# MCU.net
KiCad netlist of a schematic drawn in Altium Designer
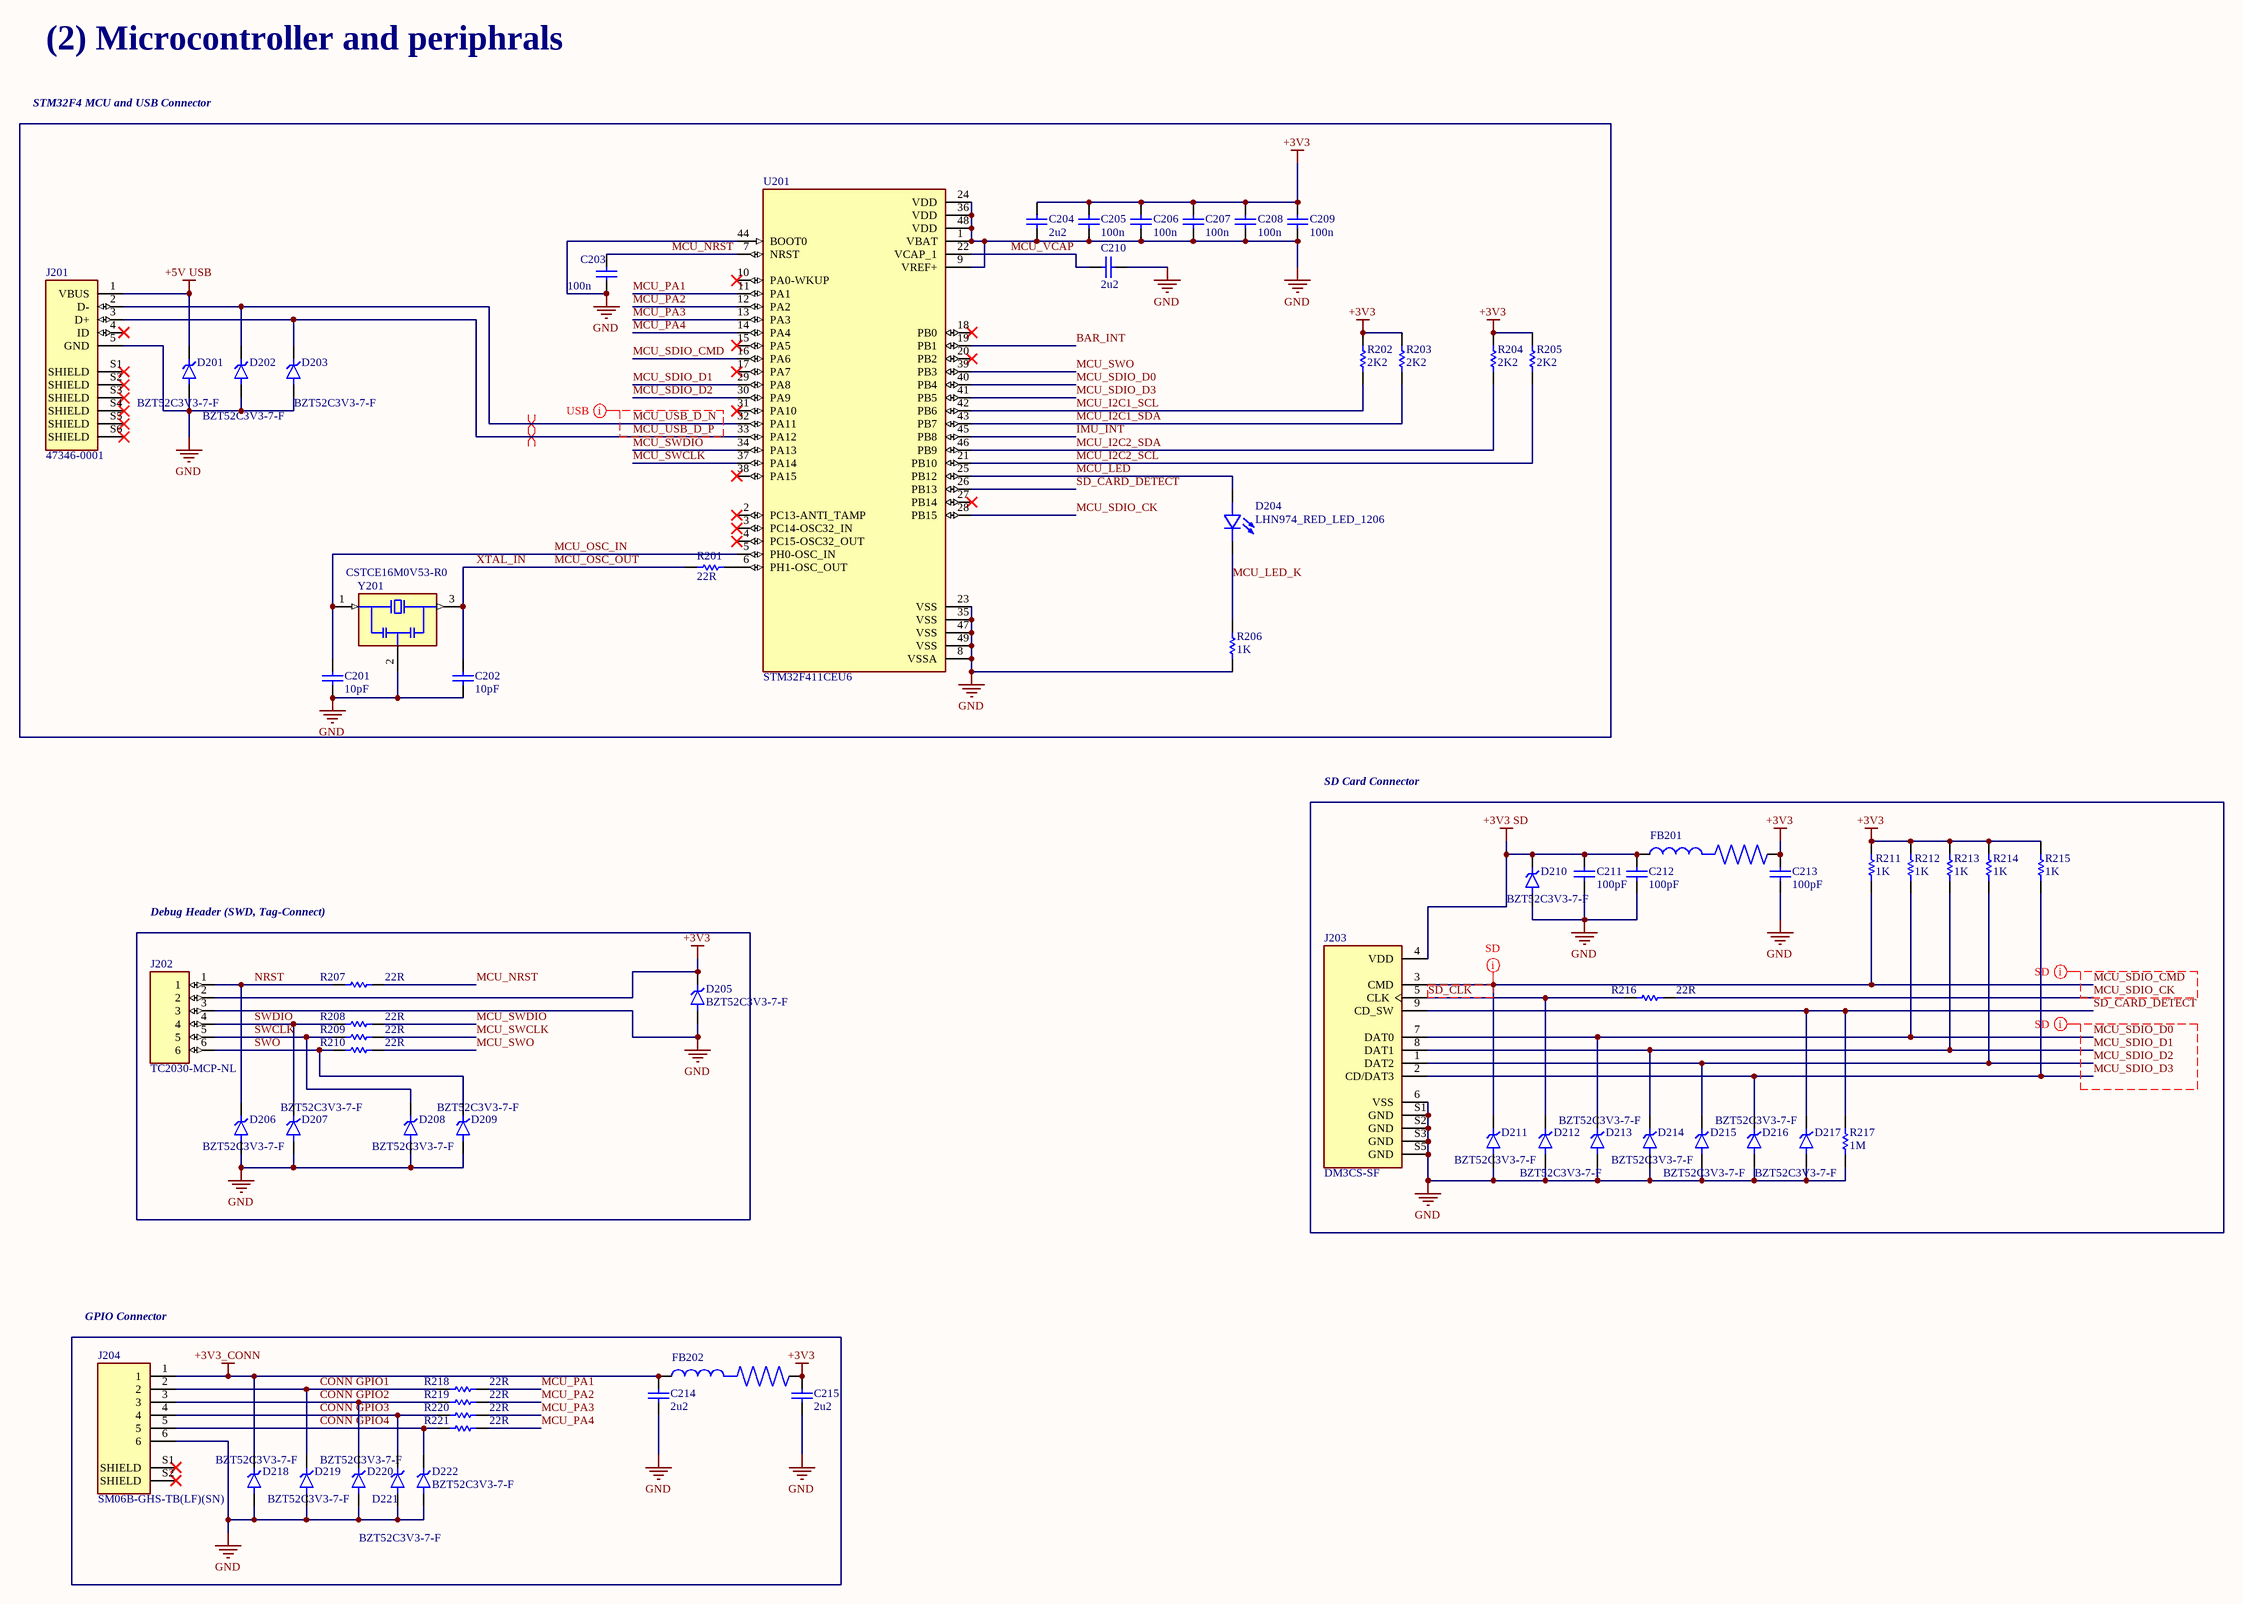
[diagram p0: MCU.SchDoc]

(export (version "E")
  (design (tool "Eeschema 10.0.6"))
  (components
    (comp (ref "C201")
      (value "10pF")
      (footprint "CAP-SM-0805")
      (description "Capacitor")
      (fields (field (name "Comment") "Cap Non-Pol SMD"))
      (libsource (lib "PIF_Library") (part "Cap Non-Pol SMD"))
    )
    (comp (ref "C202")
      (value "10pF")
      (footprint "CAP-SM-0805")
      (description "Capacitor")
      (fields (field (name "Comment") "Cap Non-Pol SMD"))
      (libsource (lib "PIF_Library") (part "Cap Non-Pol SMD"))
    )
    (comp (ref "C203")
      (value "100n")
      (footprint "CAP-SM-0805")
      (description "Capacitor")
      (fields (field (name "Comment") "Cap Non-Pol SMD"))
      (libsource (lib "PIF_Library") (part "Cap Non-Pol SMD"))
    )
    (comp (ref "C204")
      (value "2u2")
      (footprint "CAP-SM-0805")
      (description "Capacitor")
      (fields (field (name "Comment") "Cap Non-Pol SMD"))
      (libsource (lib "PIF_Library") (part "Cap Non-Pol SMD"))
    )
    (comp (ref "C205")
      (value "100n")
      (footprint "CAP-SM-0805")
      (description "Capacitor")
      (fields (field (name "Comment") "Cap Non-Pol SMD"))
      (libsource (lib "PIF_Library") (part "Cap Non-Pol SMD"))
    )
    (comp (ref "C206")
      (value "100n")
      (footprint "CAP-SM-0805")
      (description "Capacitor")
      (fields (field (name "Comment") "Cap Non-Pol SMD"))
      (libsource (lib "PIF_Library") (part "Cap Non-Pol SMD"))
    )
    (comp (ref "C207")
      (value "100n")
      (footprint "CAP-SM-0805")
      (description "Capacitor")
      (fields (field (name "Comment") "Cap Non-Pol SMD"))
      (libsource (lib "PIF_Library") (part "Cap Non-Pol SMD"))
    )
    (comp (ref "C208")
      (value "100n")
      (footprint "CAP-SM-0805")
      (description "Capacitor")
      (fields (field (name "Comment") "Cap Non-Pol SMD"))
      (libsource (lib "PIF_Library") (part "Cap Non-Pol SMD"))
    )
    (comp (ref "C209")
      (value "100n")
      (footprint "CAP-SM-0805")
      (description "Capacitor")
      (fields (field (name "Comment") "Cap Non-Pol SMD"))
      (libsource (lib "PIF_Library") (part "Cap Non-Pol SMD"))
    )
    (comp (ref "C210")
      (value "2u2")
      (footprint "CAP-SM-0805")
      (description "Capacitor")
      (fields (field (name "Comment") "Cap Non-Pol SMD"))
      (libsource (lib "PIF_Library") (part "Cap Non-Pol SMD"))
    )
    (comp (ref "C211")
      (value "100pF")
      (footprint "CAP-SM-0805")
      (description "Capacitor")
      (fields (field (name "Comment") "Cap Non-Pol SMD"))
      (libsource (lib "PIF_Library") (part "Cap Non-Pol SMD"))
    )
    (comp (ref "C212")
      (value "100pF")
      (footprint "CAP-SM-0805")
      (description "Capacitor")
      (fields (field (name "Comment") "Cap Non-Pol SMD"))
      (libsource (lib "PIF_Library") (part "Cap Non-Pol SMD"))
    )
    (comp (ref "C213")
      (value "100pF")
      (footprint "CAP-SM-0805")
      (description "Capacitor")
      (fields (field (name "Comment") "Cap Non-Pol SMD"))
      (libsource (lib "PIF_Library") (part "Cap Non-Pol SMD"))
    )
    (comp (ref "C214")
      (value "2u2")
      (footprint "CAP-SM-0805")
      (description "Capacitor")
      (fields (field (name "Comment") "Cap Non-Pol SMD"))
      (libsource (lib "PIF_Library") (part "Cap Non-Pol SMD"))
    )
    (comp (ref "C215")
      (value "2u2")
      (footprint "CAP-SM-0805")
      (description "Capacitor")
      (fields (field (name "Comment") "Cap Non-Pol SMD"))
      (libsource (lib "PIF_Library") (part "Cap Non-Pol SMD"))
    )
    (comp (ref "D201")
      (value "BZT52C3V3-7-F")
      (footprint "SOD3715X135N")
      (description "Diode Zener 3.3V 6% 500mW 2Pin SOD123 ¦ Diodes Inc BZT52C3V3-7-F")
      (fields (field (name "MF") "Diodes Inc."))
      (libsource (lib "BZT52C3V3-7-F") (part "BZT52C3V3-7-F"))
    )
    (comp (ref "D202")
      (value "BZT52C3V3-7-F")
      (footprint "SOD3715X135N")
      (description "Diode Zener 3.3V 6% 500mW 2Pin SOD123 ¦ Diodes Inc BZT52C3V3-7-F")
      (fields (field (name "MF") "Diodes Inc."))
      (libsource (lib "BZT52C3V3-7-F") (part "BZT52C3V3-7-F"))
    )
    (comp (ref "D203")
      (value "BZT52C3V3-7-F")
      (footprint "SOD3715X135N")
      (description "Diode Zener 3.3V 6% 500mW 2Pin SOD123 ¦ Diodes Inc BZT52C3V3-7-F")
      (fields (field (name "MF") "Diodes Inc."))
      (libsource (lib "BZT52C3V3-7-F") (part "BZT52C3V3-7-F"))
    )
    (comp (ref "D204")
      (value "LHN974_RED_LED_1206")
      (footprint "LEDC3216X120N")
      (description "2.6 V Red LED SMD")
      (fields (field (name "MF") "Osram") (field (name "MP") "LHN974 RED LED 1206"))
      (libsource (lib "LHN974_RED_LED_1206") (part "LHN974_RED_LED_1206"))
    )
    (comp (ref "D205")
      (value "BZT52C3V3-7-F")
      (footprint "SOD3715X135N")
      (description "Diode Zener 3.3V 6% 500mW 2Pin SOD123 ¦ Diodes Inc BZT52C3V3-7-F")
      (fields (field (name "MF") "Diodes Inc."))
      (libsource (lib "BZT52C3V3-7-F") (part "BZT52C3V3-7-F"))
    )
    (comp (ref "D206")
      (value "BZT52C3V3-7-F")
      (footprint "SOD3715X135N")
      (description "Diode Zener 3.3V 6% 500mW 2Pin SOD123 ¦ Diodes Inc BZT52C3V3-7-F")
      (fields (field (name "MF") "Diodes Inc."))
      (libsource (lib "BZT52C3V3-7-F") (part "BZT52C3V3-7-F"))
    )
    (comp (ref "D207")
      (value "BZT52C3V3-7-F")
      (footprint "SOD3715X135N")
      (description "Diode Zener 3.3V 6% 500mW 2Pin SOD123 ¦ Diodes Inc BZT52C3V3-7-F")
      (fields (field (name "MF") "Diodes Inc."))
      (libsource (lib "BZT52C3V3-7-F") (part "BZT52C3V3-7-F"))
    )
    (comp (ref "D208")
      (value "BZT52C3V3-7-F")
      (footprint "SOD3715X135N")
      (description "Diode Zener 3.3V 6% 500mW 2Pin SOD123 ¦ Diodes Inc BZT52C3V3-7-F")
      (fields (field (name "MF") "Diodes Inc."))
      (libsource (lib "BZT52C3V3-7-F") (part "BZT52C3V3-7-F"))
    )
    (comp (ref "D209")
      (value "BZT52C3V3-7-F")
      (footprint "SOD3715X135N")
      (description "Diode Zener 3.3V 6% 500mW 2Pin SOD123 ¦ Diodes Inc BZT52C3V3-7-F")
      (fields (field (name "MF") "Diodes Inc."))
      (libsource (lib "BZT52C3V3-7-F") (part "BZT52C3V3-7-F"))
    )
    (comp (ref "D210")
      (value "BZT52C3V3-7-F")
      (footprint "SOD3715X135N")
      (description "Diode Zener 3.3V 6% 500mW 2Pin SOD123 ¦ Diodes Inc BZT52C3V3-7-F")
      (fields (field (name "MF") "Diodes Inc."))
      (libsource (lib "BZT52C3V3-7-F") (part "BZT52C3V3-7-F"))
    )
    (comp (ref "D211")
      (value "BZT52C3V3-7-F")
      (footprint "SOD3715X135N")
      (description "Diode Zener 3.3V 6% 500mW 2Pin SOD123 ¦ Diodes Inc BZT52C3V3-7-F")
      (fields (field (name "MF") "Diodes Inc."))
      (libsource (lib "BZT52C3V3-7-F") (part "BZT52C3V3-7-F"))
    )
    (comp (ref "D212")
      (value "BZT52C3V3-7-F")
      (footprint "SOD3715X135N")
      (description "Diode Zener 3.3V 6% 500mW 2Pin SOD123 ¦ Diodes Inc BZT52C3V3-7-F")
      (fields (field (name "MF") "Diodes Inc."))
      (libsource (lib "BZT52C3V3-7-F") (part "BZT52C3V3-7-F"))
    )
    (comp (ref "D213")
      (value "BZT52C3V3-7-F")
      (footprint "SOD3715X135N")
      (description "Diode Zener 3.3V 6% 500mW 2Pin SOD123 ¦ Diodes Inc BZT52C3V3-7-F")
      (fields (field (name "MF") "Diodes Inc."))
      (libsource (lib "BZT52C3V3-7-F") (part "BZT52C3V3-7-F"))
    )
    (comp (ref "D214")
      (value "BZT52C3V3-7-F")
      (footprint "SOD3715X135N")
      (description "Diode Zener 3.3V 6% 500mW 2Pin SOD123 ¦ Diodes Inc BZT52C3V3-7-F")
      (fields (field (name "MF") "Diodes Inc."))
      (libsource (lib "BZT52C3V3-7-F") (part "BZT52C3V3-7-F"))
    )
    (comp (ref "D215")
      (value "BZT52C3V3-7-F")
      (footprint "SOD3715X135N")
      (description "Diode Zener 3.3V 6% 500mW 2Pin SOD123 ¦ Diodes Inc BZT52C3V3-7-F")
      (fields (field (name "MF") "Diodes Inc."))
      (libsource (lib "BZT52C3V3-7-F") (part "BZT52C3V3-7-F"))
    )
    (comp (ref "D216")
      (value "BZT52C3V3-7-F")
      (footprint "SOD3715X135N")
      (description "Diode Zener 3.3V 6% 500mW 2Pin SOD123 ¦ Diodes Inc BZT52C3V3-7-F")
      (fields (field (name "MF") "Diodes Inc."))
      (libsource (lib "BZT52C3V3-7-F") (part "BZT52C3V3-7-F"))
    )
    (comp (ref "D217")
      (value "BZT52C3V3-7-F")
      (footprint "SOD3715X135N")
      (description "Diode Zener 3.3V 6% 500mW 2Pin SOD123 ¦ Diodes Inc BZT52C3V3-7-F")
      (fields (field (name "MF") "Diodes Inc."))
      (libsource (lib "BZT52C3V3-7-F") (part "BZT52C3V3-7-F"))
    )
    (comp (ref "D218")
      (value "BZT52C3V3-7-F")
      (footprint "SOD3715X135N")
      (description "Diode Zener 3.3V 6% 500mW 2Pin SOD123 ¦ Diodes Inc BZT52C3V3-7-F")
      (fields (field (name "MF") "Diodes Inc."))
      (libsource (lib "BZT52C3V3-7-F") (part "BZT52C3V3-7-F"))
    )
    (comp (ref "D219")
      (value "BZT52C3V3-7-F")
      (footprint "SOD3715X135N")
      (description "Diode Zener 3.3V 6% 500mW 2Pin SOD123 ¦ Diodes Inc BZT52C3V3-7-F")
      (fields (field (name "MF") "Diodes Inc."))
      (libsource (lib "BZT52C3V3-7-F") (part "BZT52C3V3-7-F"))
    )
    (comp (ref "D220")
      (value "BZT52C3V3-7-F")
      (footprint "SOD3715X135N")
      (description "Diode Zener 3.3V 6% 500mW 2Pin SOD123 ¦ Diodes Inc BZT52C3V3-7-F")
      (fields (field (name "MF") "Diodes Inc."))
      (libsource (lib "BZT52C3V3-7-F") (part "BZT52C3V3-7-F"))
    )
    (comp (ref "D221")
      (value "BZT52C3V3-7-F")
      (footprint "SOD3715X135N")
      (description "Diode Zener 3.3V 6% 500mW 2Pin SOD123 ¦ Diodes Inc BZT52C3V3-7-F")
      (fields (field (name "MF") "Diodes Inc."))
      (libsource (lib "BZT52C3V3-7-F") (part "BZT52C3V3-7-F"))
    )
    (comp (ref "D222")
      (value "BZT52C3V3-7-F")
      (footprint "SOD3715X135N")
      (description "Diode Zener 3.3V 6% 500mW 2Pin SOD123 ¦ Diodes Inc BZT52C3V3-7-F")
      (fields (field (name "MF") "Diodes Inc."))
      (libsource (lib "BZT52C3V3-7-F") (part "BZT52C3V3-7-F"))
    )
    (comp (ref "FB201")
      (value "~")
      (footprint "BEADC0603X33N")
      (description "Ferrite Bead")
      (fields (field (name "MF") "Murata") (field (name "MP") "BLM03HD331SZ1D"))
      (libsource (lib "BLM03HD331SZ1D") (part "BLM03HD331SZ1D"))
    )
    (comp (ref "FB202")
      (value "~")
      (footprint "BEADC0603X33N")
      (description "Ferrite Bead")
      (fields (field (name "MF") "Murata") (field (name "MP") "BLM03HD331SZ1D"))
      (libsource (lib "BLM03HD331SZ1D") (part "BLM03HD331SZ1D"))
    )
    (comp (ref "J201")
      (value "47346-0001")
      (footprint "MOLEX_47346-0001")
      (description "Conn Data USB Micro B w/Flange SMT Bottom Mnt LF ¦ Molex Incorporated 47346-0001")
      (fields (field (name "MF") "Molex"))
      (libsource (lib "47346-0001") (part "47346-0001"))
    )
    (comp (ref "J202")
      (value "TC2030-MCP-NL")
      (footprint "TC2030-MCP-NL")
      (description "MPLABÂ® REAL ICE, ICD 3, PICkit 3, PICkit 2 Plug-Of-Nailsâ„¢ Adapter Cable")
      (fields (field (name "MF") "Tag-Connect LLC"))
      (libsource (lib "TC2030-MCP-NL") (part "TC2030-MCP-NL"))
    )
    (comp (ref "J203")
      (value "DM3CS-SF")
      (footprint "HRS_DM3CS-SF")
      (description "10 (8 + 2) Position Card Connector Secure Digital - microSDâ„¢ Surface Mount, Right Angle Gold")
      (fields (field (name "MF") "Hirose Electric Co Ltd"))
      (libsource (lib "DM3CS-SF") (part "DM3CS-SF"))
    )
    (comp (ref "J204")
      (value "SM06B-GHS-TB(LF)(SN)")
      (footprint "JST_SM06B-GHS-TB(LF)(SN)")
      (description "Connector Header Surface Mount, Right Angle 6 position 0.049 (1.25mm)")
      (fields (field (name "MF") "JST Sales") (field (name "MP") "SM06B-GHS-TB(LF)(SN)-"))
      (libsource (lib "SM06B-GHS-TB_LF__SN_") (part "SM06B-GHS-TB(LF)(SN)"))
    )
    (comp (ref "R201")
      (value "22R")
      (footprint "RES-SM-0603")
      (description "Resistor")
      (fields (field (name "Comment") "RESISTOR SMD"))
      (libsource (lib "PIF_Library") (part "RESISTOR SMD"))
    )
    (comp (ref "R202")
      (value "2K2")
      (footprint "RES-SM-0603")
      (description "Resistor")
      (fields (field (name "Comment") "RESISTOR SMD"))
      (libsource (lib "PIF_Library") (part "RESISTOR SMD"))
    )
    (comp (ref "R203")
      (value "2K2")
      (footprint "RES-SM-0603")
      (description "Resistor")
      (fields (field (name "Comment") "RESISTOR SMD"))
      (libsource (lib "PIF_Library") (part "RESISTOR SMD"))
    )
    (comp (ref "R204")
      (value "2K2")
      (footprint "RES-SM-0603")
      (description "Resistor")
      (fields (field (name "Comment") "RESISTOR SMD"))
      (libsource (lib "PIF_Library") (part "RESISTOR SMD"))
    )
    (comp (ref "R205")
      (value "2K2")
      (footprint "RES-SM-0603")
      (description "Resistor")
      (fields (field (name "Comment") "RESISTOR SMD"))
      (libsource (lib "PIF_Library") (part "RESISTOR SMD"))
    )
    (comp (ref "R206")
      (value "1K")
      (footprint "RES-SM-0603")
      (description "Resistor")
      (fields (field (name "Comment") "RESISTOR SMD"))
      (libsource (lib "PIF_Library") (part "RESISTOR SMD"))
    )
    (comp (ref "R207")
      (value "22R")
      (footprint "RES-SM-0603")
      (description "Resistor")
      (fields (field (name "Comment") "RESISTOR SMD"))
      (libsource (lib "PIF_Library") (part "RESISTOR SMD"))
    )
    (comp (ref "R208")
      (value "22R")
      (footprint "RES-SM-0603")
      (description "Resistor")
      (fields (field (name "Comment") "RESISTOR SMD"))
      (libsource (lib "PIF_Library") (part "RESISTOR SMD"))
    )
    (comp (ref "R209")
      (value "22R")
      (footprint "RES-SM-0603")
      (description "Resistor")
      (fields (field (name "Comment") "RESISTOR SMD"))
      (libsource (lib "PIF_Library") (part "RESISTOR SMD"))
    )
    (comp (ref "R210")
      (value "22R")
      (footprint "RES-SM-0603")
      (description "Resistor")
      (fields (field (name "Comment") "RESISTOR SMD"))
      (libsource (lib "PIF_Library") (part "RESISTOR SMD"))
    )
    (comp (ref "R211")
      (value "RESISTOR SMD")
      (footprint "RES-SM-0603")
      (description "Resistor")
      (fields (field (name "10K") "1K"))
      (libsource (lib "PIF_Library") (part "RESISTOR SMD"))
    )
    (comp (ref "R212")
      (value "RESISTOR SMD")
      (footprint "RES-SM-0603")
      (description "Resistor")
      (fields (field (name "10K") "1K"))
      (libsource (lib "PIF_Library") (part "RESISTOR SMD"))
    )
    (comp (ref "R213")
      (value "RESISTOR SMD")
      (footprint "RES-SM-0603")
      (description "Resistor")
      (fields (field (name "10K") "1K"))
      (libsource (lib "PIF_Library") (part "RESISTOR SMD"))
    )
    (comp (ref "R214")
      (value "RESISTOR SMD")
      (footprint "RES-SM-0603")
      (description "Resistor")
      (fields (field (name "10K") "1K"))
      (libsource (lib "PIF_Library") (part "RESISTOR SMD"))
    )
    (comp (ref "R215")
      (value "RESISTOR SMD")
      (footprint "RES-SM-0603")
      (description "Resistor")
      (fields (field (name "10K") "1K"))
      (libsource (lib "PIF_Library") (part "RESISTOR SMD"))
    )
    (comp (ref "R216")
      (value "RESISTOR SMD")
      (footprint "RES-SM-0603")
      (description "Resistor")
      (fields (field (name "R216") "22R"))
      (libsource (lib "PIF_Library") (part "RESISTOR SMD"))
    )
    (comp (ref "R217")
      (value "1M")
      (footprint "RES-SM-0603")
      (description "Resistor")
      (fields (field (name "Comment") "RESISTOR SMD"))
      (libsource (lib "PIF_Library") (part "RESISTOR SMD"))
    )
    (comp (ref "R218")
      (value "22R")
      (footprint "RES-SM-0603")
      (description "Resistor")
      (fields (field (name "Comment") "RESISTOR SMD"))
      (libsource (lib "PIF_Library") (part "RESISTOR SMD"))
    )
    (comp (ref "R219")
      (value "22R")
      (footprint "RES-SM-0603")
      (description "Resistor")
      (fields (field (name "Comment") "RESISTOR SMD"))
      (libsource (lib "PIF_Library") (part "RESISTOR SMD"))
    )
    (comp (ref "R220")
      (value "22R")
      (footprint "RES-SM-0603")
      (description "Resistor")
      (fields (field (name "Comment") "RESISTOR SMD"))
      (libsource (lib "PIF_Library") (part "RESISTOR SMD"))
    )
    (comp (ref "R221")
      (value "22R")
      (footprint "RES-SM-0603")
      (description "Resistor")
      (fields (field (name "Comment") "RESISTOR SMD"))
      (libsource (lib "PIF_Library") (part "RESISTOR SMD"))
    )
    (comp (ref "U201")
      (value "STM32F411CEU6")
      (footprint "QFN50P700X700X60-49N")
      (libsource (lib "STM32F411CEU6") (part "STM32F411CEU6"))
    )
    (comp (ref "Y201")
      (value "CSTCE16M0V53-R0")
      (footprint "OSC_CSTCE16M0V53-R0")
      (description "16 MHz Ceramic Resonator Built in Capacitor 15 pF Â±0.3% -20Â°C ~ 80Â°C Surface Mount")
      (fields (field (name "MF") "Murata") (field (name "MP") "CSTCE16M0V53-R0-"))
      (libsource (lib "CSTCE16M0V53-R0") (part "CSTCE16M0V53-R0"))
    )
  )
  (nets
    (net (code "1") (name "+3V3") (class "Default")
      (node (ref "C204") (pin "2") (pinfunction "2_2") (pintype "passive"))
      (node (ref "C205") (pin "2") (pinfunction "2_2") (pintype "passive"))
      (node (ref "C206") (pin "2") (pinfunction "2_2") (pintype "passive"))
      (node (ref "C207") (pin "2") (pinfunction "2_2") (pintype "passive"))
      (node (ref "C208") (pin "2") (pinfunction "2_2") (pintype "passive"))
      (node (ref "C209") (pin "2") (pinfunction "2_2") (pintype "passive"))
      (node (ref "C213") (pin "2") (pinfunction "2_2") (pintype "passive"))
      (node (ref "C215") (pin "2") (pinfunction "2_2") (pintype "passive"))
      (node (ref "D205") (pin "K") (pinfunction "K_K") (pintype "passive"))
      (node (ref "FB201") (pin "2") (pinfunction "2_2") (pintype "passive"))
      (node (ref "FB202") (pin "2") (pinfunction "2_2") (pintype "passive"))
      (node (ref "J202") (pin "2") (pinfunction "2_2") (pintype "bidirectional"))
      (node (ref "R202") (pin "2") (pinfunction "2_2") (pintype "passive"))
      (node (ref "R203") (pin "2") (pinfunction "2_2") (pintype "passive"))
      (node (ref "R204") (pin "2") (pinfunction "2_2") (pintype "passive"))
      (node (ref "R205") (pin "2") (pinfunction "2_2") (pintype "passive"))
      (node (ref "R211") (pin "2") (pinfunction "2_2") (pintype "passive"))
      (node (ref "R212") (pin "2") (pinfunction "2_2") (pintype "passive"))
      (node (ref "R213") (pin "2") (pinfunction "2_2") (pintype "passive"))
      (node (ref "R214") (pin "2") (pinfunction "2_2") (pintype "passive"))
      (node (ref "R215") (pin "2") (pinfunction "2_2") (pintype "passive"))
    )
    (net (code "2") (name "+3V3 SD") (class "Default")
      (node (ref "C211") (pin "2") (pinfunction "2_2") (pintype "passive"))
      (node (ref "C212") (pin "2") (pinfunction "2_2") (pintype "passive"))
      (node (ref "D210") (pin "K") (pinfunction "K_K") (pintype "passive"))
      (node (ref "FB201") (pin "1") (pinfunction "1_1") (pintype "passive"))
      (node (ref "J203") (pin "4") (pinfunction "VDD_4") (pintype "passive"))
    )
    (net (code "3") (name "+3V3_CONN") (class "Default")
      (node (ref "C214") (pin "2") (pinfunction "2_2") (pintype "passive"))
      (node (ref "D218") (pin "K") (pinfunction "K_K") (pintype "passive"))
      (node (ref "FB202") (pin "1") (pinfunction "1_1") (pintype "passive"))
      (node (ref "J204") (pin "1") (pinfunction "1_1") (pintype "passive"))
    )
    (net (code "4") (name "+5V USB") (class "Default")
      (node (ref "D201") (pin "K") (pinfunction "K_K") (pintype "passive"))
      (node (ref "J201") (pin "1") (pinfunction "VBUS_1") (pintype "power_in"))
    )
    (net (code "5") (name "/BAR_INT") (class "Default")
      (node (ref "U201") (pin "19") (pinfunction "PB1_19") (pintype "bidirectional"))
    )
    (net (code "6") (name "/CONN GPIO1") (class "Default")
      (node (ref "D219") (pin "K") (pinfunction "K_K") (pintype "passive"))
      (node (ref "J204") (pin "2") (pinfunction "2_2") (pintype "passive"))
      (node (ref "R218") (pin "2") (pinfunction "2_2") (pintype "passive"))
    )
    (net (code "7") (name "/CONN GPIO2") (class "Default")
      (node (ref "D220") (pin "K") (pinfunction "K_K") (pintype "passive"))
      (node (ref "J204") (pin "3") (pinfunction "3_3") (pintype "passive"))
      (node (ref "R219") (pin "2") (pinfunction "2_2") (pintype "passive"))
    )
    (net (code "8") (name "/CONN GPIO3") (class "Default")
      (node (ref "D221") (pin "K") (pinfunction "K_K") (pintype "passive"))
      (node (ref "J204") (pin "4") (pinfunction "4_4") (pintype "passive"))
      (node (ref "R220") (pin "2") (pinfunction "2_2") (pintype "passive"))
    )
    (net (code "9") (name "/CONN GPIO4") (class "Default")
      (node (ref "D222") (pin "K") (pinfunction "K_K") (pintype "passive"))
      (node (ref "J204") (pin "5") (pinfunction "5_5") (pintype "passive"))
      (node (ref "R221") (pin "2") (pinfunction "2_2") (pintype "passive"))
    )
    (net (code "10") (name "/IMU_INT") (class "Default")
      (node (ref "U201") (pin "45") (pinfunction "PB8_45") (pintype "bidirectional"))
    )
    (net (code "11") (name "/MCU_I2C1_SCL") (class "Default")
      (node (ref "R202") (pin "1") (pinfunction "1_1") (pintype "passive"))
      (node (ref "U201") (pin "42") (pinfunction "PB6_42") (pintype "bidirectional"))
    )
    (net (code "12") (name "/MCU_I2C1_SDA") (class "Default")
      (node (ref "R203") (pin "1") (pinfunction "1_1") (pintype "passive"))
      (node (ref "U201") (pin "43") (pinfunction "PB7_43") (pintype "bidirectional"))
    )
    (net (code "13") (name "/MCU_I2C2_SCL") (class "Default")
      (node (ref "R205") (pin "1") (pinfunction "1_1") (pintype "passive"))
      (node (ref "U201") (pin "21") (pinfunction "PB10_21") (pintype "bidirectional"))
    )
    (net (code "14") (name "/MCU_I2C2_SDA") (class "Default")
      (node (ref "R204") (pin "1") (pinfunction "1_1") (pintype "passive"))
      (node (ref "U201") (pin "46") (pinfunction "PB9_46") (pintype "bidirectional"))
    )
    (net (code "15") (name "/MCU_LED") (class "Default")
      (node (ref "D204") (pin "POS") (pinfunction "POS_POS") (pintype "passive"))
      (node (ref "U201") (pin "25") (pinfunction "PB12_25") (pintype "bidirectional"))
    )
    (net (code "16") (name "/MCU_LED_K") (class "Default")
      (node (ref "D204") (pin "NEG") (pinfunction "NEG_NEG") (pintype "passive"))
      (node (ref "R206") (pin "2") (pinfunction "2_2") (pintype "passive"))
    )
    (net (code "17") (name "/MCU_NRST") (class "Default")
      (node (ref "C203") (pin "2") (pinfunction "2_2") (pintype "passive"))
      (node (ref "R207") (pin "1") (pinfunction "1_1") (pintype "passive"))
      (node (ref "U201") (pin "7") (pinfunction "NRST_7") (pintype "bidirectional"))
    )
    (net (code "18") (name "/MCU_OSC_IN") (class "Default")
      (node (ref "C201") (pin "2") (pinfunction "2_2") (pintype "passive"))
      (node (ref "U201") (pin "5") (pinfunction "PH0-OSC_IN_5") (pintype "bidirectional"))
      (node (ref "Y201") (pin "1") (pinfunction "IN_1") (pintype "input"))
    )
    (net (code "19") (name "/MCU_OSC_OUT") (class "Default")
      (node (ref "C202") (pin "2") (pinfunction "2_2") (pintype "passive"))
      (node (ref "R201") (pin "2") (pinfunction "2_2") (pintype "passive"))
      (node (ref "Y201") (pin "3") (pinfunction "OUT_3") (pintype "output"))
    )
    (net (code "20") (name "/MCU_PA1") (class "Default")
      (node (ref "R218") (pin "1") (pinfunction "1_1") (pintype "passive"))
      (node (ref "U201") (pin "11") (pinfunction "PA1_11") (pintype "bidirectional"))
    )
    (net (code "21") (name "/MCU_PA2") (class "Default")
      (node (ref "R219") (pin "1") (pinfunction "1_1") (pintype "passive"))
      (node (ref "U201") (pin "12") (pinfunction "PA2_12") (pintype "bidirectional"))
    )
    (net (code "22") (name "/MCU_PA3") (class "Default")
      (node (ref "R220") (pin "1") (pinfunction "1_1") (pintype "passive"))
      (node (ref "U201") (pin "13") (pinfunction "PA3_13") (pintype "bidirectional"))
    )
    (net (code "23") (name "/MCU_PA4") (class "Default")
      (node (ref "R221") (pin "1") (pinfunction "1_1") (pintype "passive"))
      (node (ref "U201") (pin "14") (pinfunction "PA4_14") (pintype "bidirectional"))
    )
    (net (code "24") (name "/MCU_SDIO_CK") (class "Default")
      (node (ref "R216") (pin "1") (pinfunction "1_1") (pintype "passive"))
      (node (ref "U201") (pin "28") (pinfunction "PB15_28") (pintype "bidirectional"))
    )
    (net (code "25") (name "/MCU_SDIO_CMD") (class "Default")
      (node (ref "D211") (pin "K") (pinfunction "K_K") (pintype "passive"))
      (node (ref "J203") (pin "3") (pinfunction "CMD_3") (pintype "passive"))
      (node (ref "R211") (pin "1") (pinfunction "1_1") (pintype "passive"))
      (node (ref "U201") (pin "16") (pinfunction "PA6_16") (pintype "bidirectional"))
    )
    (net (code "26") (name "/MCU_SDIO_D0") (class "Default")
      (node (ref "D213") (pin "K") (pinfunction "K_K") (pintype "passive"))
      (node (ref "J203") (pin "7") (pinfunction "DAT0_7") (pintype "passive"))
      (node (ref "R212") (pin "1") (pinfunction "1_1") (pintype "passive"))
      (node (ref "U201") (pin "40") (pinfunction "PB4_40") (pintype "bidirectional"))
    )
    (net (code "27") (name "/MCU_SDIO_D1") (class "Default")
      (node (ref "D214") (pin "K") (pinfunction "K_K") (pintype "passive"))
      (node (ref "J203") (pin "8") (pinfunction "DAT1_8") (pintype "passive"))
      (node (ref "R213") (pin "1") (pinfunction "1_1") (pintype "passive"))
      (node (ref "U201") (pin "29") (pinfunction "PA8_29") (pintype "bidirectional"))
    )
    (net (code "28") (name "/MCU_SDIO_D2") (class "Default")
      (node (ref "D215") (pin "K") (pinfunction "K_K") (pintype "passive"))
      (node (ref "J203") (pin "1") (pinfunction "DAT2_1") (pintype "passive"))
      (node (ref "R214") (pin "1") (pinfunction "1_1") (pintype "passive"))
      (node (ref "U201") (pin "30") (pinfunction "PA9_30") (pintype "bidirectional"))
    )
    (net (code "29") (name "/MCU_SDIO_D3") (class "Default")
      (node (ref "D216") (pin "K") (pinfunction "K_K") (pintype "passive"))
      (node (ref "J203") (pin "2") (pinfunction "CD/DAT3_2") (pintype "passive"))
      (node (ref "R215") (pin "1") (pinfunction "1_1") (pintype "passive"))
      (node (ref "U201") (pin "41") (pinfunction "PB5_41") (pintype "bidirectional"))
    )
    (net (code "30") (name "/MCU_SWCLK") (class "Default")
      (node (ref "R209") (pin "1") (pinfunction "1_1") (pintype "passive"))
      (node (ref "U201") (pin "37") (pinfunction "PA14_37") (pintype "bidirectional"))
    )
    (net (code "31") (name "/MCU_SWDIO") (class "Default")
      (node (ref "R208") (pin "1") (pinfunction "1_1") (pintype "passive"))
      (node (ref "U201") (pin "34") (pinfunction "PA13_34") (pintype "bidirectional"))
    )
    (net (code "32") (name "/MCU_SWO") (class "Default")
      (node (ref "R210") (pin "1") (pinfunction "1_1") (pintype "passive"))
      (node (ref "U201") (pin "39") (pinfunction "PB3_39") (pintype "bidirectional"))
    )
    (net (code "33") (name "/MCU_USB_D_N") (class "Default")
      (node (ref "D202") (pin "K") (pinfunction "K_K") (pintype "passive"))
      (node (ref "J201") (pin "2") (pinfunction "D-_2") (pintype "bidirectional"))
      (node (ref "U201") (pin "32") (pinfunction "PA11_32") (pintype "bidirectional"))
    )
    (net (code "34") (name "/MCU_USB_D_P") (class "Default")
      (node (ref "D203") (pin "K") (pinfunction "K_K") (pintype "passive"))
      (node (ref "J201") (pin "3") (pinfunction "D+_3") (pintype "bidirectional"))
      (node (ref "U201") (pin "33") (pinfunction "PA12_33") (pintype "bidirectional"))
    )
    (net (code "35") (name "/MCU_VCAP") (class "Default")
      (node (ref "C210") (pin "2") (pinfunction "2_2") (pintype "passive"))
      (node (ref "U201") (pin "22") (pinfunction "VCAP_1_22") (pintype "power_in"))
    )
    (net (code "36") (name "/NRST") (class "Default")
      (node (ref "D206") (pin "K") (pinfunction "K_K") (pintype "passive"))
      (node (ref "J202") (pin "1") (pinfunction "1_1") (pintype "bidirectional"))
      (node (ref "R207") (pin "2") (pinfunction "2_2") (pintype "passive"))
    )
    (net (code "37") (name "/SD_CARD_DETECT") (class "Default")
      (node (ref "D217") (pin "K") (pinfunction "K_K") (pintype "passive"))
      (node (ref "J203") (pin "9") (pinfunction "CD_SW_9") (pintype "passive"))
      (node (ref "R217") (pin "2") (pinfunction "2_2") (pintype "passive"))
      (node (ref "U201") (pin "26") (pinfunction "PB13_26") (pintype "bidirectional"))
    )
    (net (code "38") (name "/SD_CLK") (class "Default")
      (node (ref "D212") (pin "K") (pinfunction "K_K") (pintype "passive"))
      (node (ref "J203") (pin "5") (pinfunction "CLK_5") (pintype "passive"))
      (node (ref "R216") (pin "2") (pinfunction "2_2") (pintype "passive"))
    )
    (net (code "39") (name "/SWCLK") (class "Default")
      (node (ref "D208") (pin "K") (pinfunction "K_K") (pintype "passive"))
      (node (ref "J202") (pin "5") (pinfunction "5_5") (pintype "bidirectional"))
      (node (ref "R209") (pin "2") (pinfunction "2_2") (pintype "passive"))
    )
    (net (code "40") (name "/SWDIO") (class "Default")
      (node (ref "D207") (pin "K") (pinfunction "K_K") (pintype "passive"))
      (node (ref "J202") (pin "4") (pinfunction "4_4") (pintype "bidirectional"))
      (node (ref "R208") (pin "2") (pinfunction "2_2") (pintype "passive"))
    )
    (net (code "41") (name "/SWO") (class "Default")
      (node (ref "D209") (pin "K") (pinfunction "K_K") (pintype "passive"))
      (node (ref "J202") (pin "6") (pinfunction "6_6") (pintype "bidirectional"))
      (node (ref "R210") (pin "2") (pinfunction "2_2") (pintype "passive"))
    )
    (net (code "42") (name "GND") (class "Default")
      (node (ref "C201") (pin "1") (pinfunction "1_1") (pintype "passive"))
      (node (ref "C202") (pin "1") (pinfunction "1_1") (pintype "passive"))
      (node (ref "C203") (pin "1") (pinfunction "1_1") (pintype "passive"))
      (node (ref "C204") (pin "1") (pinfunction "1_1") (pintype "passive"))
      (node (ref "C205") (pin "1") (pinfunction "1_1") (pintype "passive"))
      (node (ref "C206") (pin "1") (pinfunction "1_1") (pintype "passive"))
      (node (ref "C207") (pin "1") (pinfunction "1_1") (pintype "passive"))
      (node (ref "C208") (pin "1") (pinfunction "1_1") (pintype "passive"))
      (node (ref "C209") (pin "1") (pinfunction "1_1") (pintype "passive"))
      (node (ref "C210") (pin "1") (pinfunction "1_1") (pintype "passive"))
      (node (ref "C211") (pin "1") (pinfunction "1_1") (pintype "passive"))
      (node (ref "C212") (pin "1") (pinfunction "1_1") (pintype "passive"))
      (node (ref "C213") (pin "1") (pinfunction "1_1") (pintype "passive"))
      (node (ref "C214") (pin "1") (pinfunction "1_1") (pintype "passive"))
      (node (ref "C215") (pin "1") (pinfunction "1_1") (pintype "passive"))
      (node (ref "D201") (pin "A") (pinfunction "A_A") (pintype "passive"))
      (node (ref "D202") (pin "A") (pinfunction "A_A") (pintype "passive"))
      (node (ref "D203") (pin "A") (pinfunction "A_A") (pintype "passive"))
      (node (ref "D205") (pin "A") (pinfunction "A_A") (pintype "passive"))
      (node (ref "D206") (pin "A") (pinfunction "A_A") (pintype "passive"))
      (node (ref "D207") (pin "A") (pinfunction "A_A") (pintype "passive"))
      (node (ref "D208") (pin "A") (pinfunction "A_A") (pintype "passive"))
      (node (ref "D209") (pin "A") (pinfunction "A_A") (pintype "passive"))
      (node (ref "D210") (pin "A") (pinfunction "A_A") (pintype "passive"))
      (node (ref "D211") (pin "A") (pinfunction "A_A") (pintype "passive"))
      (node (ref "D212") (pin "A") (pinfunction "A_A") (pintype "passive"))
      (node (ref "D213") (pin "A") (pinfunction "A_A") (pintype "passive"))
      (node (ref "D214") (pin "A") (pinfunction "A_A") (pintype "passive"))
      (node (ref "D215") (pin "A") (pinfunction "A_A") (pintype "passive"))
      (node (ref "D216") (pin "A") (pinfunction "A_A") (pintype "passive"))
      (node (ref "D217") (pin "A") (pinfunction "A_A") (pintype "passive"))
      (node (ref "D218") (pin "A") (pinfunction "A_A") (pintype "passive"))
      (node (ref "D219") (pin "A") (pinfunction "A_A") (pintype "passive"))
      (node (ref "D220") (pin "A") (pinfunction "A_A") (pintype "passive"))
      (node (ref "D221") (pin "A") (pinfunction "A_A") (pintype "passive"))
      (node (ref "D222") (pin "A") (pinfunction "A_A") (pintype "passive"))
      (node (ref "J201") (pin "5") (pinfunction "GND_5") (pintype "power_in"))
      (node (ref "J202") (pin "3") (pinfunction "3_3") (pintype "bidirectional"))
      (node (ref "J203") (pin "6") (pinfunction "VSS_6") (pintype "passive"))
      (node (ref "J203") (pin "S1") (pinfunction "GND_S1") (pintype "passive"))
      (node (ref "J203") (pin "S2") (pinfunction "GND_S2") (pintype "passive"))
      (node (ref "J203") (pin "S3") (pinfunction "GND_S3") (pintype "passive"))
      (node (ref "J203") (pin "S5") (pinfunction "GND_S5") (pintype "passive"))
      (node (ref "J204") (pin "6") (pinfunction "6_6") (pintype "passive"))
      (node (ref "R206") (pin "1") (pinfunction "1_1") (pintype "passive"))
      (node (ref "R217") (pin "1") (pinfunction "1_1") (pintype "passive"))
      (node (ref "U201") (pin "1") (pinfunction "VBAT_1") (pintype "power_in"))
      (node (ref "U201") (pin "23") (pinfunction "VSS_23") (pintype "power_in"))
      (node (ref "U201") (pin "24") (pinfunction "VDD_24") (pintype "power_in"))
      (node (ref "U201") (pin "35") (pinfunction "VSS_35") (pintype "power_in"))
      (node (ref "U201") (pin "36") (pinfunction "VDD_36") (pintype "power_in"))
      (node (ref "U201") (pin "44") (pinfunction "BOOT0_44") (pintype "input"))
      (node (ref "U201") (pin "47") (pinfunction "VSS_47") (pintype "power_in"))
      (node (ref "U201") (pin "48") (pinfunction "VDD_48") (pintype "power_in"))
      (node (ref "U201") (pin "49") (pinfunction "VSS_49") (pintype "power_in"))
      (node (ref "U201") (pin "8") (pinfunction "VSSA_8") (pintype "power_in"))
      (node (ref "U201") (pin "9") (pinfunction "VREF+_9") (pintype "power_in"))
      (node (ref "Y201") (pin "2") (pinfunction "GND_2") (pintype "power_in"))
    )
    (net (code "43") (name "Net-(U201-PH1-OSC_OUT)") (class "Default")
      (node (ref "R201") (pin "1") (pinfunction "1_1") (pintype "passive"))
      (node (ref "U201") (pin "6") (pinfunction "PH1-OSC_OUT_6") (pintype "bidirectional"))
    )
    (net (code "44") (name "unconnected-(J201-ID-Pad4)") (class "Default")
      (node (ref "J201") (pin "4") (pinfunction "ID_4") (pintype "bidirectional+no_connect"))
    )
    (net (code "45") (name "unconnected-(J201-SHIELD-PadS1)") (class "Default")
      (node (ref "J201") (pin "S1") (pinfunction "SHIELD_S1") (pintype "passive+no_connect"))
    )
    (net (code "46") (name "unconnected-(J201-SHIELD-PadS2)") (class "Default")
      (node (ref "J201") (pin "S2") (pinfunction "SHIELD_S2") (pintype "passive+no_connect"))
    )
    (net (code "47") (name "unconnected-(J201-SHIELD-PadS3)") (class "Default")
      (node (ref "J201") (pin "S3") (pinfunction "SHIELD_S3") (pintype "passive+no_connect"))
    )
    (net (code "48") (name "unconnected-(J201-SHIELD-PadS4)") (class "Default")
      (node (ref "J201") (pin "S4") (pinfunction "SHIELD_S4") (pintype "passive+no_connect"))
    )
    (net (code "49") (name "unconnected-(J201-SHIELD-PadS5)") (class "Default")
      (node (ref "J201") (pin "S5") (pinfunction "SHIELD_S5") (pintype "passive+no_connect"))
    )
    (net (code "50") (name "unconnected-(J201-SHIELD-PadS6)") (class "Default")
      (node (ref "J201") (pin "S6") (pinfunction "SHIELD_S6") (pintype "passive+no_connect"))
    )
    (net (code "51") (name "unconnected-(J204-SHIELD-PadS1)") (class "Default")
      (node (ref "J204") (pin "S1") (pinfunction "SHIELD_S1") (pintype "passive+no_connect"))
    )
    (net (code "52") (name "unconnected-(J204-SHIELD-PadS2)") (class "Default")
      (node (ref "J204") (pin "S2") (pinfunction "SHIELD_S2") (pintype "passive+no_connect"))
    )
    (net (code "53") (name "unconnected-(U201-PA0-WKUP-Pad10)") (class "Default")
      (node (ref "U201") (pin "10") (pinfunction "PA0-WKUP_10") (pintype "bidirectional+no_connect"))
    )
    (net (code "54") (name "unconnected-(U201-PA5-Pad15)") (class "Default")
      (node (ref "U201") (pin "15") (pinfunction "PA5_15") (pintype "bidirectional+no_connect"))
    )
    (net (code "55") (name "unconnected-(U201-PA7-Pad17)") (class "Default")
      (node (ref "U201") (pin "17") (pinfunction "PA7_17") (pintype "bidirectional+no_connect"))
    )
    (net (code "56") (name "unconnected-(U201-PA10-Pad31)") (class "Default")
      (node (ref "U201") (pin "31") (pinfunction "PA10_31") (pintype "bidirectional+no_connect"))
    )
    (net (code "57") (name "unconnected-(U201-PA15-Pad38)") (class "Default")
      (node (ref "U201") (pin "38") (pinfunction "PA15_38") (pintype "bidirectional+no_connect"))
    )
    (net (code "58") (name "unconnected-(U201-PB0-Pad18)") (class "Default")
      (node (ref "U201") (pin "18") (pinfunction "PB0_18") (pintype "bidirectional+no_connect"))
    )
    (net (code "59") (name "unconnected-(U201-PB2-Pad20)") (class "Default")
      (node (ref "U201") (pin "20") (pinfunction "PB2_20") (pintype "bidirectional+no_connect"))
    )
    (net (code "60") (name "unconnected-(U201-PB14-Pad27)") (class "Default")
      (node (ref "U201") (pin "27") (pinfunction "PB14_27") (pintype "bidirectional+no_connect"))
    )
    (net (code "61") (name "unconnected-(U201-PC13-ANTI_TAMP-Pad2)") (class "Default")
      (node (ref "U201") (pin "2") (pinfunction "PC13-ANTI_TAMP_2") (pintype "bidirectional+no_connect"))
    )
    (net (code "62") (name "unconnected-(U201-PC14-OSC32_IN-Pad3)") (class "Default")
      (node (ref "U201") (pin "3") (pinfunction "PC14-OSC32_IN_3") (pintype "bidirectional+no_connect"))
    )
    (net (code "63") (name "unconnected-(U201-PC15-OSC32_OUT-Pad4)") (class "Default")
      (node (ref "U201") (pin "4") (pinfunction "PC15-OSC32_OUT_4") (pintype "bidirectional+no_connect"))
    )
  )
)
